# FPGA_PowerConnection.net
KiCad netlist of a schematic drawn in Altium Designer
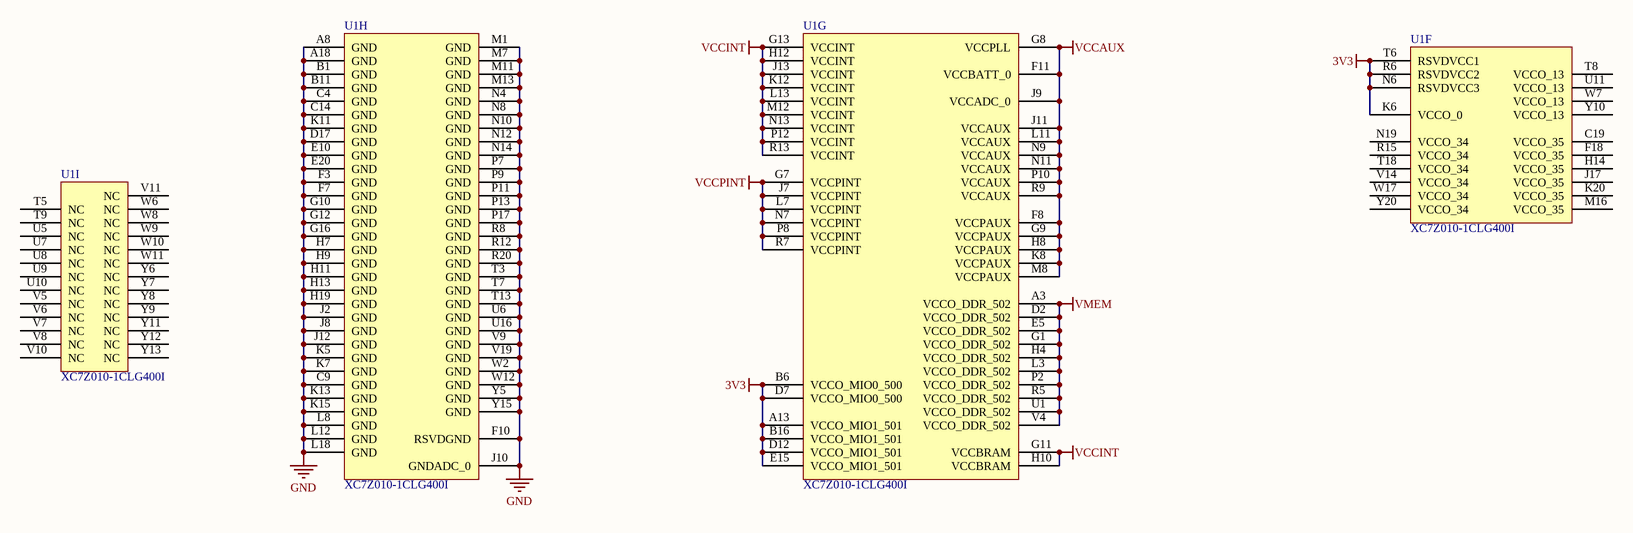
[diagram p0: FPGA_PowerConnection.SchDoc]

(export (version "E")
  (design (tool "Eeschema 10.0.6"))
  (components
    (comp (ref "U1")
      (value "XC7Z010-1CLG400I")
      (footprint "CLG400")
      (fields (field (name "GENERIC PART NUMBER") "XC7Z010"))
      (libsource (lib "Altium Content Vault") (part "XNLX-XC7Z010-CLG400"))
    )
  )
  (nets
    (net (code "1") (name "3V3") (class "Default")
      (node (ref "U1") (pin "A13") (pinfunction "VCCO_MIO1_501_A13") (pintype "power_in"))
      (node (ref "U1") (pin "B16") (pinfunction "VCCO_MIO1_501_B16") (pintype "power_in"))
      (node (ref "U1") (pin "B6") (pinfunction "VCCO_MIO0_500_B6") (pintype "power_in"))
      (node (ref "U1") (pin "D12") (pinfunction "VCCO_MIO1_501_D12") (pintype "power_in"))
      (node (ref "U1") (pin "D7") (pinfunction "VCCO_MIO0_500_D7") (pintype "power_in"))
      (node (ref "U1") (pin "E15") (pinfunction "VCCO_MIO1_501_E15") (pintype "power_in"))
      (node (ref "U1") (pin "K6") (pinfunction "VCCO_0_K6") (pintype "power_in"))
      (node (ref "U1") (pin "N6") (pinfunction "RSVDVCC3_N6") (pintype "power_in"))
      (node (ref "U1") (pin "R6") (pinfunction "RSVDVCC2_R6") (pintype "power_in"))
      (node (ref "U1") (pin "T6") (pinfunction "RSVDVCC1_T6") (pintype "power_in"))
    )
    (net (code "2") (name "GND") (class "Default")
      (node (ref "U1") (pin "A18") (pinfunction "GND_A18") (pintype "power_in"))
      (node (ref "U1") (pin "A8") (pinfunction "GND_A8") (pintype "power_in"))
      (node (ref "U1") (pin "B1") (pinfunction "GND_B1") (pintype "power_in"))
      (node (ref "U1") (pin "B11") (pinfunction "GND_B11") (pintype "power_in"))
      (node (ref "U1") (pin "C14") (pinfunction "GND_C14") (pintype "power_in"))
      (node (ref "U1") (pin "C4") (pinfunction "GND_C4") (pintype "power_in"))
      (node (ref "U1") (pin "C9") (pinfunction "GND_C9") (pintype "power_in"))
      (node (ref "U1") (pin "D17") (pinfunction "GND_D17") (pintype "power_in"))
      (node (ref "U1") (pin "E10") (pinfunction "GND_E10") (pintype "power_in"))
      (node (ref "U1") (pin "E20") (pinfunction "GND_E20") (pintype "power_in"))
      (node (ref "U1") (pin "F10") (pinfunction "RSVDGND_F10") (pintype "power_in"))
      (node (ref "U1") (pin "F3") (pinfunction "GND_F3") (pintype "power_in"))
      (node (ref "U1") (pin "F7") (pinfunction "GND_F7") (pintype "power_in"))
      (node (ref "U1") (pin "G10") (pinfunction "GND_G10") (pintype "power_in"))
      (node (ref "U1") (pin "G12") (pinfunction "GND_G12") (pintype "power_in"))
      (node (ref "U1") (pin "G16") (pinfunction "GND_G16") (pintype "power_in"))
      (node (ref "U1") (pin "H11") (pinfunction "GND_H11") (pintype "power_in"))
      (node (ref "U1") (pin "H13") (pinfunction "GND_H13") (pintype "power_in"))
      (node (ref "U1") (pin "H19") (pinfunction "GND_H19") (pintype "power_in"))
      (node (ref "U1") (pin "H7") (pinfunction "GND_H7") (pintype "power_in"))
      (node (ref "U1") (pin "H9") (pinfunction "GND_H9") (pintype "power_in"))
      (node (ref "U1") (pin "J10") (pinfunction "GNDADC_0_J10") (pintype "power_in"))
      (node (ref "U1") (pin "J12") (pinfunction "GND_J12") (pintype "power_in"))
      (node (ref "U1") (pin "J2") (pinfunction "GND_J2") (pintype "power_in"))
      (node (ref "U1") (pin "J8") (pinfunction "GND_J8") (pintype "power_in"))
      (node (ref "U1") (pin "K11") (pinfunction "GND_K11") (pintype "power_in"))
      (node (ref "U1") (pin "K13") (pinfunction "GND_K13") (pintype "power_in"))
      (node (ref "U1") (pin "K15") (pinfunction "GND_K15") (pintype "power_in"))
      (node (ref "U1") (pin "K5") (pinfunction "GND_K5") (pintype "power_in"))
      (node (ref "U1") (pin "K7") (pinfunction "GND_K7") (pintype "power_in"))
      (node (ref "U1") (pin "L12") (pinfunction "GND_L12") (pintype "power_in"))
      (node (ref "U1") (pin "L18") (pinfunction "GND_L18") (pintype "power_in"))
      (node (ref "U1") (pin "L8") (pinfunction "GND_L8") (pintype "power_in"))
      (node (ref "U1") (pin "M1") (pinfunction "GND_M1") (pintype "power_in"))
      (node (ref "U1") (pin "M11") (pinfunction "GND_M11") (pintype "power_in"))
      (node (ref "U1") (pin "M13") (pinfunction "GND_M13") (pintype "power_in"))
      (node (ref "U1") (pin "M7") (pinfunction "GND_M7") (pintype "power_in"))
      (node (ref "U1") (pin "N10") (pinfunction "GND_N10") (pintype "power_in"))
      (node (ref "U1") (pin "N12") (pinfunction "GND_N12") (pintype "power_in"))
      (node (ref "U1") (pin "N14") (pinfunction "GND_N14") (pintype "power_in"))
      (node (ref "U1") (pin "N4") (pinfunction "GND_N4") (pintype "power_in"))
      (node (ref "U1") (pin "N8") (pinfunction "GND_N8") (pintype "power_in"))
      (node (ref "U1") (pin "P11") (pinfunction "GND_P11") (pintype "power_in"))
      (node (ref "U1") (pin "P13") (pinfunction "GND_P13") (pintype "power_in"))
      (node (ref "U1") (pin "P17") (pinfunction "GND_P17") (pintype "power_in"))
      (node (ref "U1") (pin "P7") (pinfunction "GND_P7") (pintype "power_in"))
      (node (ref "U1") (pin "P9") (pinfunction "GND_P9") (pintype "power_in"))
      (node (ref "U1") (pin "R12") (pinfunction "GND_R12") (pintype "power_in"))
      (node (ref "U1") (pin "R20") (pinfunction "GND_R20") (pintype "power_in"))
      (node (ref "U1") (pin "R8") (pinfunction "GND_R8") (pintype "power_in"))
      (node (ref "U1") (pin "T13") (pinfunction "GND_T13") (pintype "power_in"))
      (node (ref "U1") (pin "T3") (pinfunction "GND_T3") (pintype "power_in"))
      (node (ref "U1") (pin "T7") (pinfunction "GND_T7") (pintype "power_in"))
      (node (ref "U1") (pin "U16") (pinfunction "GND_U16") (pintype "power_in"))
      (node (ref "U1") (pin "U6") (pinfunction "GND_U6") (pintype "power_in"))
      (node (ref "U1") (pin "V19") (pinfunction "GND_V19") (pintype "power_in"))
      (node (ref "U1") (pin "V9") (pinfunction "GND_V9") (pintype "power_in"))
      (node (ref "U1") (pin "W12") (pinfunction "GND_W12") (pintype "power_in"))
      (node (ref "U1") (pin "W2") (pinfunction "GND_W2") (pintype "power_in"))
      (node (ref "U1") (pin "Y15") (pinfunction "GND_Y15") (pintype "power_in"))
      (node (ref "U1") (pin "Y5") (pinfunction "GND_Y5") (pintype "power_in"))
    )
    (net (code "3") (name "VCCAUX") (class "Default")
      (node (ref "U1") (pin "F11") (pinfunction "VCCBATT_0_F11") (pintype "power_in"))
      (node (ref "U1") (pin "F8") (pinfunction "VCCPAUX_F8") (pintype "power_in"))
      (node (ref "U1") (pin "G8") (pinfunction "VCCPLL_G8") (pintype "power_in"))
      (node (ref "U1") (pin "G9") (pinfunction "VCCPAUX_G9") (pintype "power_in"))
      (node (ref "U1") (pin "H8") (pinfunction "VCCPAUX_H8") (pintype "power_in"))
      (node (ref "U1") (pin "J11") (pinfunction "VCCAUX_J11") (pintype "power_in"))
      (node (ref "U1") (pin "J9") (pinfunction "VCCADC_0_J9") (pintype "power_in"))
      (node (ref "U1") (pin "K8") (pinfunction "VCCPAUX_K8") (pintype "power_in"))
      (node (ref "U1") (pin "L11") (pinfunction "VCCAUX_L11") (pintype "power_in"))
      (node (ref "U1") (pin "M8") (pinfunction "VCCPAUX_M8") (pintype "power_in"))
      (node (ref "U1") (pin "N11") (pinfunction "VCCAUX_N11") (pintype "power_in"))
      (node (ref "U1") (pin "N9") (pinfunction "VCCAUX_N9") (pintype "power_in"))
      (node (ref "U1") (pin "P10") (pinfunction "VCCAUX_P10") (pintype "power_in"))
      (node (ref "U1") (pin "R9") (pinfunction "VCCAUX_R9") (pintype "power_in"))
    )
    (net (code "4") (name "VCCINT") (class "Default")
      (node (ref "U1") (pin "G11") (pinfunction "VCCBRAM_G11") (pintype "power_in"))
      (node (ref "U1") (pin "G13") (pinfunction "VCCINT_G13") (pintype "power_in"))
      (node (ref "U1") (pin "H10") (pinfunction "VCCBRAM_H10") (pintype "power_in"))
      (node (ref "U1") (pin "H12") (pinfunction "VCCINT_H12") (pintype "power_in"))
      (node (ref "U1") (pin "J13") (pinfunction "VCCINT_J13") (pintype "power_in"))
      (node (ref "U1") (pin "K12") (pinfunction "VCCINT_K12") (pintype "power_in"))
      (node (ref "U1") (pin "L13") (pinfunction "VCCINT_L13") (pintype "power_in"))
      (node (ref "U1") (pin "M12") (pinfunction "VCCINT_M12") (pintype "power_in"))
      (node (ref "U1") (pin "N13") (pinfunction "VCCINT_N13") (pintype "power_in"))
      (node (ref "U1") (pin "P12") (pinfunction "VCCINT_P12") (pintype "power_in"))
      (node (ref "U1") (pin "R13") (pinfunction "VCCINT_R13") (pintype "power_in"))
    )
    (net (code "5") (name "VCCPINT") (class "Default")
      (node (ref "U1") (pin "G7") (pinfunction "VCCPINT_G7") (pintype "power_in"))
      (node (ref "U1") (pin "J7") (pinfunction "VCCPINT_J7") (pintype "power_in"))
      (node (ref "U1") (pin "L7") (pinfunction "VCCPINT_L7") (pintype "power_in"))
      (node (ref "U1") (pin "N7") (pinfunction "VCCPINT_N7") (pintype "power_in"))
      (node (ref "U1") (pin "P8") (pinfunction "VCCPINT_P8") (pintype "power_in"))
      (node (ref "U1") (pin "R7") (pinfunction "VCCPINT_R7") (pintype "power_in"))
    )
    (net (code "6") (name "VMEM") (class "Default")
      (node (ref "U1") (pin "A3") (pinfunction "VCCO_DDR_502_A3") (pintype "power_in"))
      (node (ref "U1") (pin "D2") (pinfunction "VCCO_DDR_502_D2") (pintype "power_in"))
      (node (ref "U1") (pin "E5") (pinfunction "VCCO_DDR_502_E5") (pintype "power_in"))
      (node (ref "U1") (pin "G1") (pinfunction "VCCO_DDR_502_G1") (pintype "power_in"))
      (node (ref "U1") (pin "H4") (pinfunction "VCCO_DDR_502_H4") (pintype "power_in"))
      (node (ref "U1") (pin "L3") (pinfunction "VCCO_DDR_502_L3") (pintype "power_in"))
      (node (ref "U1") (pin "P2") (pinfunction "VCCO_DDR_502_P2") (pintype "power_in"))
      (node (ref "U1") (pin "R5") (pinfunction "VCCO_DDR_502_R5") (pintype "power_in"))
      (node (ref "U1") (pin "U1") (pinfunction "VCCO_DDR_502_U1") (pintype "power_in"))
      (node (ref "U1") (pin "V4") (pinfunction "VCCO_DDR_502_V4") (pintype "power_in"))
    )
    (net (code "7") (name "unconnected-(U1F-VCCO_13-PadT8)") (class "Default")
      (node (ref "U1") (pin "T8") (pinfunction "VCCO_13_T8") (pintype "power_in"))
    )
    (net (code "8") (name "unconnected-(U1F-VCCO_13-PadU11)") (class "Default")
      (node (ref "U1") (pin "U11") (pinfunction "VCCO_13_U11") (pintype "power_in"))
    )
    (net (code "9") (name "unconnected-(U1F-VCCO_13-PadW7)") (class "Default")
      (node (ref "U1") (pin "W7") (pinfunction "VCCO_13_W7") (pintype "power_in"))
    )
    (net (code "10") (name "unconnected-(U1F-VCCO_13-PadY10)") (class "Default")
      (node (ref "U1") (pin "Y10") (pinfunction "VCCO_13_Y10") (pintype "power_in"))
    )
    (net (code "11") (name "unconnected-(U1F-VCCO_34-PadN19)") (class "Default")
      (node (ref "U1") (pin "N19") (pinfunction "VCCO_34_N19") (pintype "power_in"))
    )
    (net (code "12") (name "unconnected-(U1F-VCCO_34-PadR15)") (class "Default")
      (node (ref "U1") (pin "R15") (pinfunction "VCCO_34_R15") (pintype "power_in"))
    )
    (net (code "13") (name "unconnected-(U1F-VCCO_34-PadT18)") (class "Default")
      (node (ref "U1") (pin "T18") (pinfunction "VCCO_34_T18") (pintype "power_in"))
    )
    (net (code "14") (name "unconnected-(U1F-VCCO_34-PadV14)") (class "Default")
      (node (ref "U1") (pin "V14") (pinfunction "VCCO_34_V14") (pintype "power_in"))
    )
    (net (code "15") (name "unconnected-(U1F-VCCO_34-PadW17)") (class "Default")
      (node (ref "U1") (pin "W17") (pinfunction "VCCO_34_W17") (pintype "power_in"))
    )
    (net (code "16") (name "unconnected-(U1F-VCCO_34-PadY20)") (class "Default")
      (node (ref "U1") (pin "Y20") (pinfunction "VCCO_34_Y20") (pintype "power_in"))
    )
    (net (code "17") (name "unconnected-(U1F-VCCO_35-PadC19)") (class "Default")
      (node (ref "U1") (pin "C19") (pinfunction "VCCO_35_C19") (pintype "power_in"))
    )
    (net (code "18") (name "unconnected-(U1F-VCCO_35-PadF18)") (class "Default")
      (node (ref "U1") (pin "F18") (pinfunction "VCCO_35_F18") (pintype "power_in"))
    )
    (net (code "19") (name "unconnected-(U1F-VCCO_35-PadH14)") (class "Default")
      (node (ref "U1") (pin "H14") (pinfunction "VCCO_35_H14") (pintype "power_in"))
    )
    (net (code "20") (name "unconnected-(U1F-VCCO_35-PadJ17)") (class "Default")
      (node (ref "U1") (pin "J17") (pinfunction "VCCO_35_J17") (pintype "power_in"))
    )
    (net (code "21") (name "unconnected-(U1F-VCCO_35-PadK20)") (class "Default")
      (node (ref "U1") (pin "K20") (pinfunction "VCCO_35_K20") (pintype "power_in"))
    )
    (net (code "22") (name "unconnected-(U1F-VCCO_35-PadM16)") (class "Default")
      (node (ref "U1") (pin "M16") (pinfunction "VCCO_35_M16") (pintype "power_in"))
    )
    (net (code "23") (name "unconnected-(U1I-NC-PadT5)") (class "Default")
      (node (ref "U1") (pin "T5") (pinfunction "NC_T5") (pintype "passive"))
    )
    (net (code "24") (name "unconnected-(U1I-NC-PadT9)") (class "Default")
      (node (ref "U1") (pin "T9") (pinfunction "NC_T9") (pintype "passive"))
    )
    (net (code "25") (name "unconnected-(U1I-NC-PadU5)") (class "Default")
      (node (ref "U1") (pin "U5") (pinfunction "NC_U5") (pintype "passive"))
    )
    (net (code "26") (name "unconnected-(U1I-NC-PadU7)") (class "Default")
      (node (ref "U1") (pin "U7") (pinfunction "NC_U7") (pintype "passive"))
    )
    (net (code "27") (name "unconnected-(U1I-NC-PadU8)") (class "Default")
      (node (ref "U1") (pin "U8") (pinfunction "NC_U8") (pintype "passive"))
    )
    (net (code "28") (name "unconnected-(U1I-NC-PadU9)") (class "Default")
      (node (ref "U1") (pin "U9") (pinfunction "NC_U9") (pintype "passive"))
    )
    (net (code "29") (name "unconnected-(U1I-NC-PadU10)") (class "Default")
      (node (ref "U1") (pin "U10") (pinfunction "NC_U10") (pintype "passive"))
    )
    (net (code "30") (name "unconnected-(U1I-NC-PadV5)") (class "Default")
      (node (ref "U1") (pin "V5") (pinfunction "NC_V5") (pintype "passive"))
    )
    (net (code "31") (name "unconnected-(U1I-NC-PadV6)") (class "Default")
      (node (ref "U1") (pin "V6") (pinfunction "NC_V6") (pintype "passive"))
    )
    (net (code "32") (name "unconnected-(U1I-NC-PadV7)") (class "Default")
      (node (ref "U1") (pin "V7") (pinfunction "NC_V7") (pintype "passive"))
    )
    (net (code "33") (name "unconnected-(U1I-NC-PadV8)") (class "Default")
      (node (ref "U1") (pin "V8") (pinfunction "NC_V8") (pintype "passive"))
    )
    (net (code "34") (name "unconnected-(U1I-NC-PadV10)") (class "Default")
      (node (ref "U1") (pin "V10") (pinfunction "NC_V10") (pintype "passive"))
    )
    (net (code "35") (name "unconnected-(U1I-NC-PadV11)") (class "Default")
      (node (ref "U1") (pin "V11") (pinfunction "NC_V11") (pintype "passive"))
    )
    (net (code "36") (name "unconnected-(U1I-NC-PadW6)") (class "Default")
      (node (ref "U1") (pin "W6") (pinfunction "NC_W6") (pintype "passive"))
    )
    (net (code "37") (name "unconnected-(U1I-NC-PadW8)") (class "Default")
      (node (ref "U1") (pin "W8") (pinfunction "NC_W8") (pintype "passive"))
    )
    (net (code "38") (name "unconnected-(U1I-NC-PadW9)") (class "Default")
      (node (ref "U1") (pin "W9") (pinfunction "NC_W9") (pintype "passive"))
    )
    (net (code "39") (name "unconnected-(U1I-NC-PadW10)") (class "Default")
      (node (ref "U1") (pin "W10") (pinfunction "NC_W10") (pintype "passive"))
    )
    (net (code "40") (name "unconnected-(U1I-NC-PadW11)") (class "Default")
      (node (ref "U1") (pin "W11") (pinfunction "NC_W11") (pintype "passive"))
    )
    (net (code "41") (name "unconnected-(U1I-NC-PadY6)") (class "Default")
      (node (ref "U1") (pin "Y6") (pinfunction "NC_Y6") (pintype "passive"))
    )
    (net (code "42") (name "unconnected-(U1I-NC-PadY7)") (class "Default")
      (node (ref "U1") (pin "Y7") (pinfunction "NC_Y7") (pintype "passive"))
    )
    (net (code "43") (name "unconnected-(U1I-NC-PadY8)") (class "Default")
      (node (ref "U1") (pin "Y8") (pinfunction "NC_Y8") (pintype "passive"))
    )
    (net (code "44") (name "unconnected-(U1I-NC-PadY9)") (class "Default")
      (node (ref "U1") (pin "Y9") (pinfunction "NC_Y9") (pintype "passive"))
    )
    (net (code "45") (name "unconnected-(U1I-NC-PadY11)") (class "Default")
      (node (ref "U1") (pin "Y11") (pinfunction "NC_Y11") (pintype "passive"))
    )
    (net (code "46") (name "unconnected-(U1I-NC-PadY12)") (class "Default")
      (node (ref "U1") (pin "Y12") (pinfunction "NC_Y12") (pintype "passive"))
    )
    (net (code "47") (name "unconnected-(U1I-NC-PadY13)") (class "Default")
      (node (ref "U1") (pin "Y13") (pinfunction "NC_Y13") (pintype "passive"))
    )
  )
)
